# voltage_sensor.net
KiCad netlist of a schematic drawn in Altium Designer
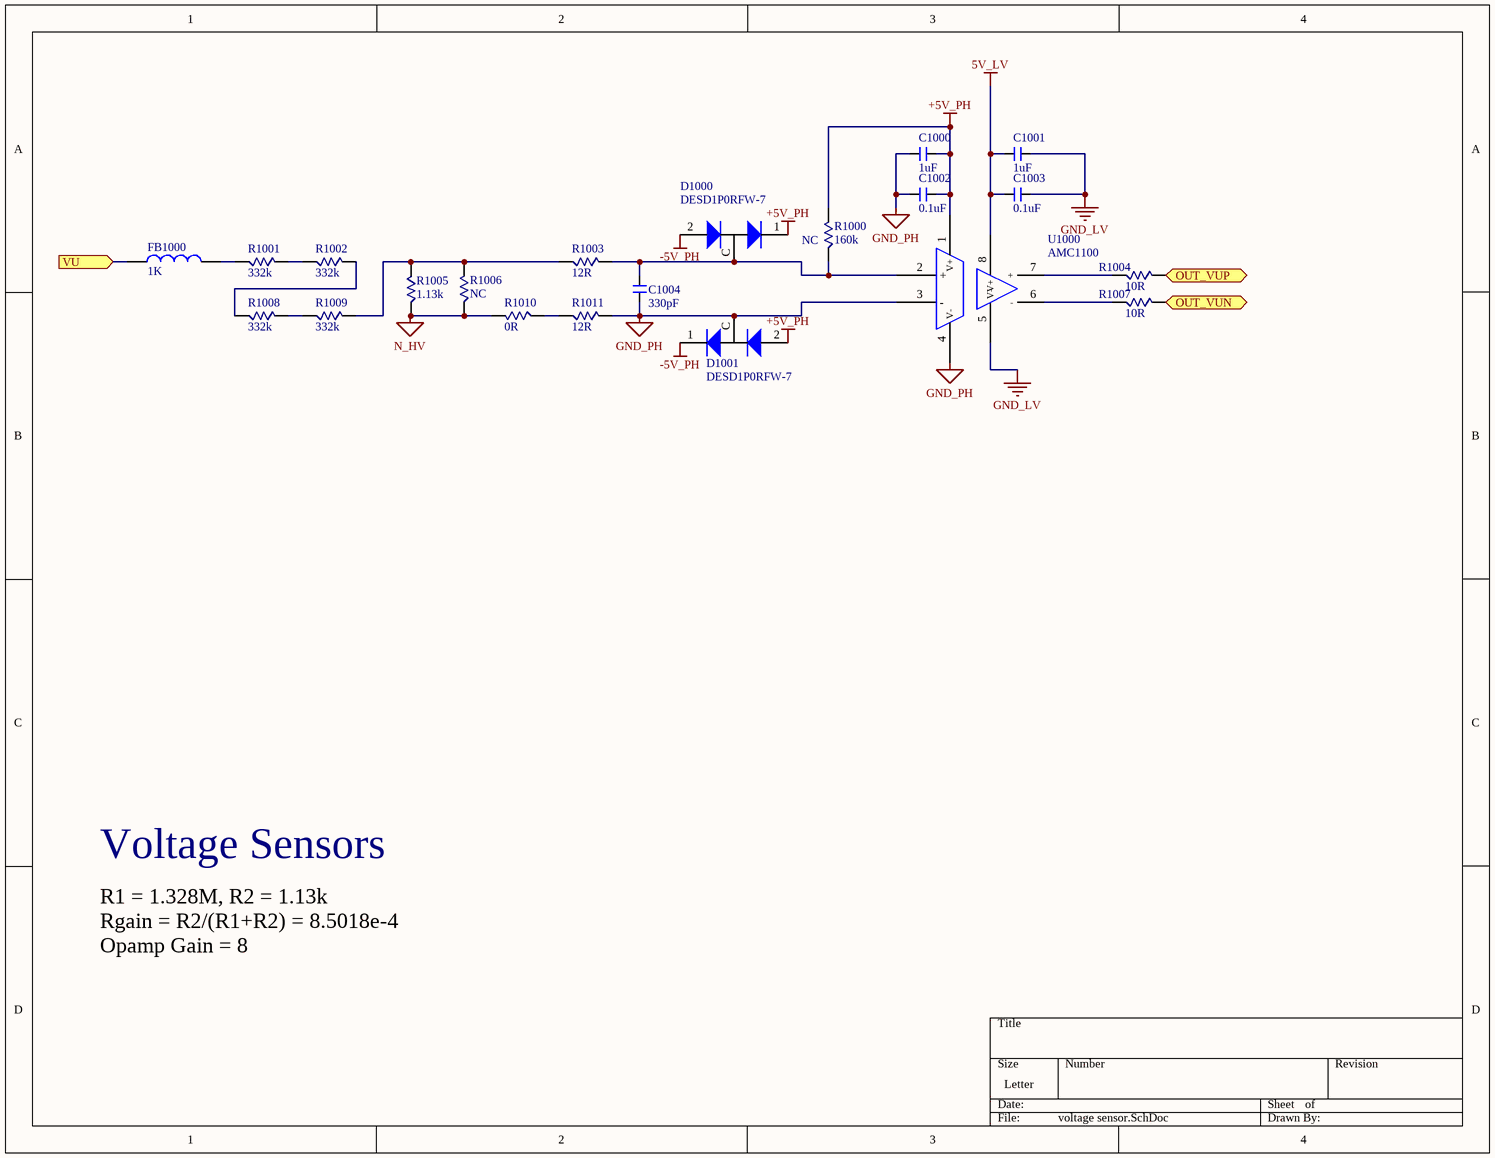
[diagram p0: voltage sensor.SchDoc]

(export (version "E")
  (design (tool "Eeschema 10.0.6"))
  (components
    (comp (ref "C1000")
      (value "1uF")
      (footprint "0603 (1608 Metric)")
      (description "CAP CER 1UF 50V X5R 0603")
      (fields (field (name "PART") "1276-1860-1-ND") (field (name "Comment") "Cap 0603_new"))
      (libsource (lib "Library_Microgrid") (part "Cap 0603_new"))
    )
    (comp (ref "C1001")
      (value "1uF")
      (footprint "0603 (1608 Metric)")
      (description "CAP CER 1UF 50V X5R 0603")
      (fields (field (name "PART") "1276-1860-1-ND") (field (name "Comment") "Cap 0603_new"))
      (libsource (lib "Library_Microgrid") (part "Cap 0603_new"))
    )
    (comp (ref "C1002")
      (value "0.1uF")
      (footprint "0603 (1608 Metric)")
      (description "CAP CER 0.1UF 50V Y5V 0603")
      (fields (field (name "PART") "311-1343-6-ND") (field (name "Comment") "Cap 0603_new"))
      (libsource (lib "Library_Microgrid") (part "Cap 0603_new"))
    )
    (comp (ref "C1003")
      (value "0.1uF")
      (footprint "0603 (1608 Metric)")
      (description "CAP CER 0.1UF 50V Y5V 0603")
      (fields (field (name "PART") "311-1343-6-ND") (field (name "Comment") "Cap 0603_new"))
      (libsource (lib "Library_Microgrid") (part "Cap 0603_new"))
    )
    (comp (ref "C1004")
      (value "330pF")
      (footprint "0603 (1608 Metric)")
      (description "CAP CER 330PF 50V C0G 0603")
      (fields (field (name "PART") "445-7033-2-ND") (field (name "Comment") "Cap 0603_new"))
      (libsource (lib "Library_Microgrid") (part "Cap 0603_new"))
    )
    (comp (ref "D1000")
      (value "Diode_ESD")
      (footprint "SOT323_ESD")
      (fields (field (name "PART") "DESD1P0RFW-7"))
      (libsource (lib "Library_Microgrid") (part "Diode_ESD"))
    )
    (comp (ref "D1001")
      (value "Diode_ESD")
      (footprint "SOT323_ESD")
      (fields (field (name "PART") "DESD1P0RFW-7"))
      (libsource (lib "Library_Microgrid") (part "Diode_ESD"))
    )
    (comp (ref "FB1000")
      (value "1K")
      (footprint "0603 (1608 Metric)")
      (description "FERRITE BEAD 1 KOHM 0603 1LN")
      (fields (field (name "PART") "445-8672-1-ND") (field (name "Comment") "Ferrite bead"))
      (libsource (lib "Library_Microgrid") (part "Ferrite bead"))
    )
    (comp (ref "R1000")
      (value "NC")
      (footprint "0603 (1608 Metric)")
      (description "Resistor 0603")
      (fields (field (name "ALTIUM_VALUE") "160k"))
      (libsource (lib "Library_Microgrid") (part "Resistor 0603"))
    )
    (comp (ref "R1001")
      (value "332k")
      (footprint "1206")
      (description "RES SMD 332K OHM 0.1% 1/4W 1206")
      (fields (field (name "PART") "RG32P332KBCT-ND") (field (name "Comment") "Resistor 1206"))
      (libsource (lib "Library_Microgrid") (part "Resistor 1206"))
    )
    (comp (ref "R1002")
      (value "332k")
      (footprint "1206")
      (description "RES SMD 332K OHM 0.1% 1/4W 1206")
      (fields (field (name "PART") "RG32P332KBCT-ND") (field (name "Comment") "Resistor 1206"))
      (libsource (lib "Library_Microgrid") (part "Resistor 1206"))
    )
    (comp (ref "R1003")
      (value "12R")
      (footprint "1206")
      (description "12 Ohm ±0.5% 0.25W, 1/4W Chip Resistor 1206")
      (fields (field (name "PART") "311-2961-1-ND") (field (name "Comment") "Resistor 1206"))
      (libsource (lib "Library_Microgrid") (part "Resistor 1206"))
    )
    (comp (ref "R1004")
      (value "10R")
      (footprint "0603 (1608 Metric)")
      (description "RES SMD 10 OHM 0.05% 1/10W 0603")
      (fields (field (name "PART") "RNCF0603AKT10R0CT-ND") (field (name "Comment") "Resistor 0603"))
      (libsource (lib "Library_Microgrid") (part "Resistor 0603"))
    )
    (comp (ref "R1005")
      (value "1.13k")
      (footprint "1206")
      (description "RES SMD 1.13K OHM 0.1% 1/4W 1206")
      (fields (field (name "PART") "P1.13KBCCT-ND") (field (name "Comment") "Resistor 1206"))
      (libsource (lib "Library_Microgrid") (part "Resistor 1206"))
    )
    (comp (ref "R1006")
      (value "NC")
      (footprint "1206")
      (fields (field (name "Comment") "Resistor 1206"))
      (libsource (lib "Library_Microgrid") (part "Resistor 1206"))
    )
    (comp (ref "R1007")
      (value "10R")
      (footprint "0603 (1608 Metric)")
      (description "RES SMD 10 OHM 0.05% 1/10W 0603")
      (fields (field (name "PART") "RNCF0603AKT10R0CT-ND") (field (name "Comment") "Resistor 0603"))
      (libsource (lib "Library_Microgrid") (part "Resistor 0603"))
    )
    (comp (ref "R1008")
      (value "332k")
      (footprint "1206")
      (description "RES SMD 332K OHM 0.1% 1/4W 1206")
      (fields (field (name "PART") "RG32P332KBCT-ND") (field (name "Comment") "Resistor 1206"))
      (libsource (lib "Library_Microgrid") (part "Resistor 1206"))
    )
    (comp (ref "R1009")
      (value "332k")
      (footprint "1206")
      (description "RES SMD 332K OHM 0.1% 1/4W 1206")
      (fields (field (name "PART") "RG32P332KBCT-ND") (field (name "Comment") "Resistor 1206"))
      (libsource (lib "Library_Microgrid") (part "Resistor 1206"))
    )
    (comp (ref "R1010")
      (value "0R")
      (footprint "0603 (1608 Metric)")
      (fields (field (name "Comment") "Resistor 0603"))
      (libsource (lib "Library_Microgrid") (part "Resistor 0603"))
    )
    (comp (ref "R1011")
      (value "12R")
      (footprint "1206")
      (description "12 Ohm ±0.5% 0.25W, 1/4W Chip Resistor 1206")
      (fields (field (name "PART") "311-2961-1-ND") (field (name "Comment") "Resistor 1206"))
      (libsource (lib "Library_Microgrid") (part "Resistor 1206"))
    )
    (comp (ref "U1000")
      (value "AMC1100")
      (footprint "SOP8")
      (libsource (lib "Library_Microgrid") (part "AMC1100"))
    )
  )
  (nets
    (net (code "1") (name "+5V_PH") (class "Default")
      (node (ref "C1000") (pin "2") (pinfunction "OUT_2") (pintype "passive"))
      (node (ref "C1002") (pin "2") (pinfunction "OUT_2") (pintype "passive"))
      (node (ref "D1000") (pin "1") (pinfunction "Anode_1") (pintype "passive"))
      (node (ref "D1001") (pin "2") (pinfunction "Anode_2") (pintype "passive"))
      (node (ref "R1000") (pin "2") (pinfunction "A_2") (pintype "passive"))
      (node (ref "U1000") (pin "1") (pinfunction "V+_1") (pintype "passive"))
    )
    (net (code "2") (name "-5V_PH") (class "Default")
      (node (ref "D1000") (pin "2") (pinfunction "Anode_2") (pintype "passive"))
      (node (ref "D1001") (pin "1") (pinfunction "Anode_1") (pintype "passive"))
    )
    (net (code "3") (name "/OUT_VUN") (class "Default")
      (node (ref "R1007") (pin "2") (pinfunction "A_2") (pintype "passive"))
    )
    (net (code "4") (name "/OUT_VUP") (class "Default")
      (node (ref "R1004") (pin "2") (pinfunction "A_2") (pintype "passive"))
    )
    (net (code "5") (name "/VU") (class "Default")
      (node (ref "FB1000") (pin "1") (pinfunction "OUT_1") (pintype "passive"))
    )
    (net (code "6") (name "5V_LV") (class "Default")
      (node (ref "C1001") (pin "1") (pinfunction "OUT_1") (pintype "passive"))
      (node (ref "C1003") (pin "1") (pinfunction "OUT_1") (pintype "passive"))
      (node (ref "U1000") (pin "8") (pinfunction "V+_8") (pintype "passive"))
    )
    (net (code "7") (name "GND_LV") (class "Default")
      (node (ref "C1001") (pin "2") (pinfunction "OUT_2") (pintype "passive"))
      (node (ref "C1003") (pin "2") (pinfunction "OUT_2") (pintype "passive"))
      (node (ref "U1000") (pin "5") (pinfunction "V-_5") (pintype "passive"))
    )
    (net (code "8") (name "GND_PH") (class "Default")
      (node (ref "C1000") (pin "1") (pinfunction "OUT_1") (pintype "passive"))
      (node (ref "C1002") (pin "1") (pinfunction "OUT_1") (pintype "passive"))
      (node (ref "C1004") (pin "2") (pinfunction "OUT_2") (pintype "passive"))
      (node (ref "D1001") (pin "C") (pinfunction "Cathode_C") (pintype "passive"))
      (node (ref "R1011") (pin "2") (pinfunction "A_2") (pintype "passive"))
      (node (ref "U1000") (pin "3") (pinfunction "-_3") (pintype "passive"))
      (node (ref "U1000") (pin "4") (pinfunction "V-_4") (pintype "passive"))
    )
    (net (code "9") (name "N_HV") (class "Default")
      (node (ref "R1005") (pin "1") (pinfunction "A_1") (pintype "passive"))
      (node (ref "R1006") (pin "1") (pinfunction "A_1") (pintype "passive"))
      (node (ref "R1010") (pin "2") (pinfunction "A_2") (pintype "passive"))
    )
    (net (code "10") (name "Net-(D1000-Cathode)") (class "Default")
      (node (ref "C1004") (pin "1") (pinfunction "OUT_1") (pintype "passive"))
      (node (ref "D1000") (pin "C") (pinfunction "Cathode_C") (pintype "passive"))
      (node (ref "R1000") (pin "1") (pinfunction "A_1") (pintype "passive"))
      (node (ref "R1003") (pin "2") (pinfunction "A_2") (pintype "passive"))
      (node (ref "U1000") (pin "2") (pinfunction "+_2") (pintype "passive"))
    )
    (net (code "11") (name "Net-(FB1000-OUT-Pad2)") (class "Default")
      (node (ref "FB1000") (pin "2") (pinfunction "OUT_2") (pintype "passive"))
      (node (ref "R1001") (pin "1") (pinfunction "A_1") (pintype "passive"))
    )
    (net (code "12") (name "Net-(R1001-A-Pad2)") (class "Default")
      (node (ref "R1001") (pin "2") (pinfunction "A_2") (pintype "passive"))
      (node (ref "R1002") (pin "1") (pinfunction "A_1") (pintype "passive"))
    )
    (net (code "13") (name "Net-(R1002-A-Pad2)") (class "Default")
      (node (ref "R1002") (pin "2") (pinfunction "A_2") (pintype "passive"))
      (node (ref "R1008") (pin "1") (pinfunction "A_1") (pintype "passive"))
    )
    (net (code "14") (name "Net-(R1003-A-Pad1)") (class "Default")
      (node (ref "R1003") (pin "1") (pinfunction "A_1") (pintype "passive"))
      (node (ref "R1005") (pin "2") (pinfunction "A_2") (pintype "passive"))
      (node (ref "R1006") (pin "2") (pinfunction "A_2") (pintype "passive"))
      (node (ref "R1009") (pin "2") (pinfunction "A_2") (pintype "passive"))
    )
    (net (code "15") (name "Net-(R1004-A-Pad1)") (class "Default")
      (node (ref "R1004") (pin "1") (pinfunction "A_1") (pintype "passive"))
      (node (ref "U1000") (pin "7") (pinfunction "+_7") (pintype "passive"))
    )
    (net (code "16") (name "Net-(R1007-A-Pad1)") (class "Default")
      (node (ref "R1007") (pin "1") (pinfunction "A_1") (pintype "passive"))
      (node (ref "U1000") (pin "6") (pinfunction "-_6") (pintype "passive"))
    )
    (net (code "17") (name "Net-(R1008-A-Pad2)") (class "Default")
      (node (ref "R1008") (pin "2") (pinfunction "A_2") (pintype "passive"))
      (node (ref "R1009") (pin "1") (pinfunction "A_1") (pintype "passive"))
    )
    (net (code "18") (name "Net-(R1010-A-Pad1)") (class "Default")
      (node (ref "R1010") (pin "1") (pinfunction "A_1") (pintype "passive"))
      (node (ref "R1011") (pin "1") (pinfunction "A_1") (pintype "passive"))
    )
  )
)
